# bpf-3rd-order.net
KiCad netlist of a schematic drawn in EAGLE
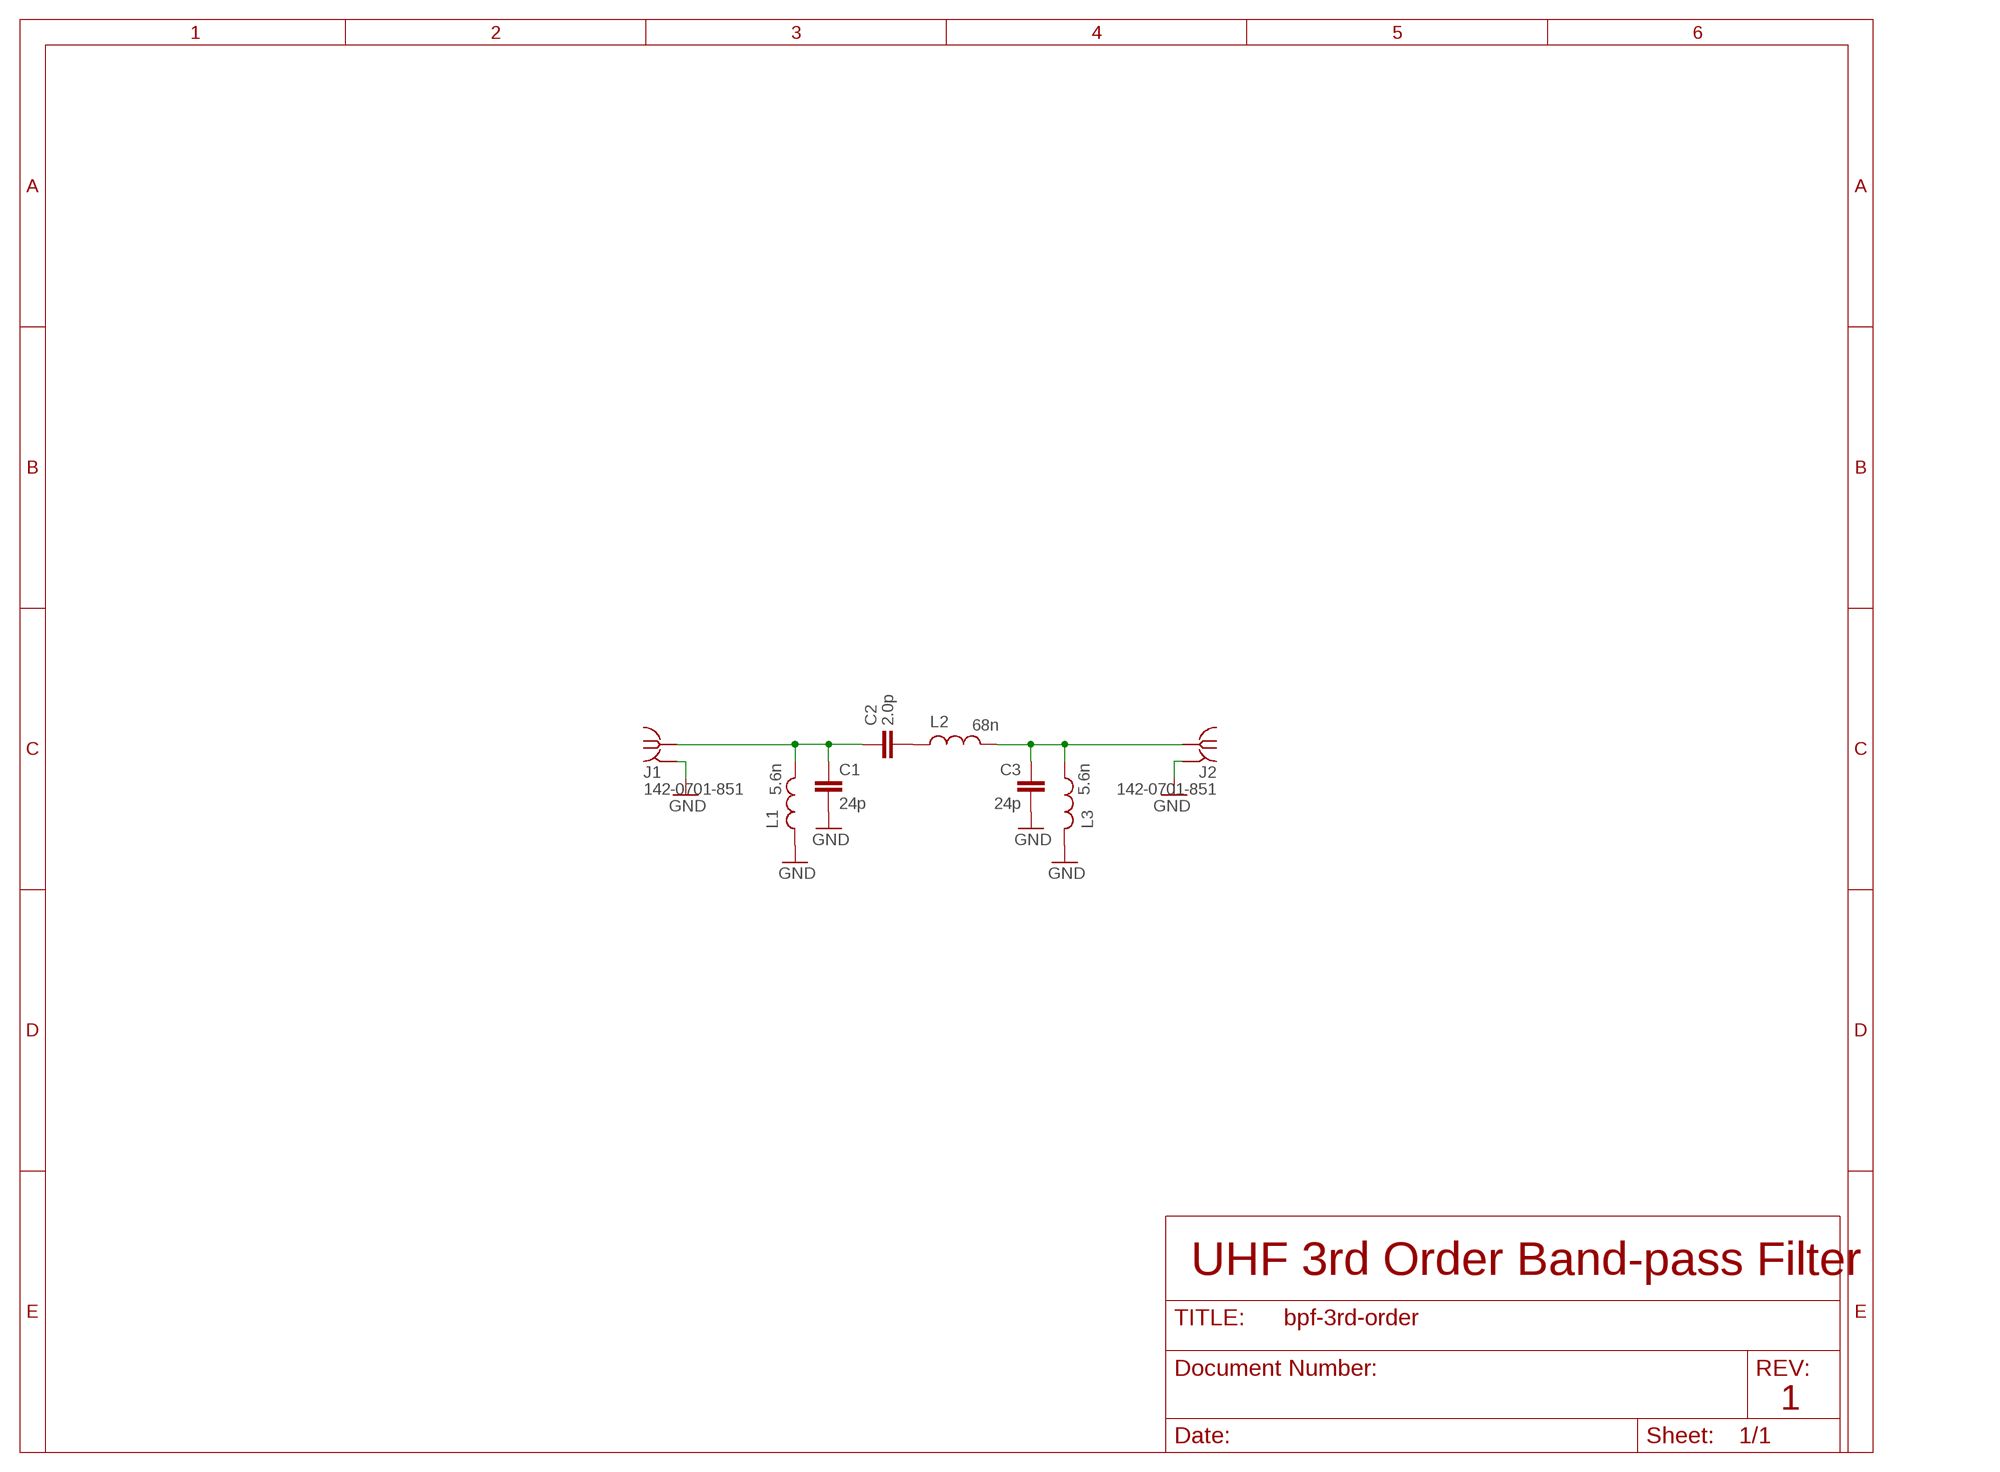
[diagram p0: schematic, sheet 1]

(export (version "E")
  (design (tool "Eeschema 10.0.6"))
  (components
    (comp (ref "C1")
      (value "24p")
      (footprint "eagle-import:.0402-C-NOSILK")
      (libsource (lib "eagle-import") (part "C-EU0402-C-NOSILK"))
    )
    (comp (ref "C2")
      (value "2.0p")
      (footprint "eagle-import:.0402-C-NOSILK")
      (libsource (lib "eagle-import") (part "C-EU0402-C-NOSILK"))
    )
    (comp (ref "C3")
      (value "24p")
      (footprint "eagle-import:.0402-C-NOSILK")
      (libsource (lib "eagle-import") (part "C-EU0402-C-NOSILK"))
    )
    (comp (ref "J1")
      (value "142-0701-851")
      (footprint "eagle-import:142-0701-851")
      (libsource (lib "eagle-import") (part "142-0701-851"))
    )
    (comp (ref "J2")
      (value "142-0701-851")
      (footprint "eagle-import:142-0701-851")
      (libsource (lib "eagle-import") (part "142-0701-851"))
    )
    (comp (ref "L1")
      (value "5.6n")
      (footprint "eagle-import:.0402-C-NOSILK")
      (libsource (lib "eagle-import") (part "L-US0402-C-NOSILK"))
    )
    (comp (ref "L2")
      (value "68n")
      (footprint "eagle-import:.0402-C-NOSILK")
      (libsource (lib "eagle-import") (part "L-US0402-C-NOSILK"))
    )
    (comp (ref "L3")
      (value "5.6n")
      (footprint "eagle-import:.0402-C-NOSILK")
      (libsource (lib "eagle-import") (part "L-US0402-C-NOSILK"))
    )
  )
  (nets
    (net (code "1") (name "GND") (class "Default")
      (node (ref "C1") (pin "2") (pinfunction "2_2") (pintype "passive"))
      (node (ref "C3") (pin "2") (pinfunction "2_2") (pintype "passive"))
      (node (ref "J1") (pin "GND1") (pinfunction "GND_GND1") (pintype "bidirectional"))
      (node (ref "J1") (pin "GND2") (pinfunction "GND_GND2") (pintype "bidirectional"))
      (node (ref "J1") (pin "GND3") (pinfunction "GND_GND3") (pintype "bidirectional"))
      (node (ref "J1") (pin "GND4") (pinfunction "GND_GND4") (pintype "bidirectional"))
      (node (ref "J2") (pin "GND1") (pinfunction "GND_GND1") (pintype "bidirectional"))
      (node (ref "J2") (pin "GND2") (pinfunction "GND_GND2") (pintype "bidirectional"))
      (node (ref "J2") (pin "GND3") (pinfunction "GND_GND3") (pintype "bidirectional"))
      (node (ref "J2") (pin "GND4") (pinfunction "GND_GND4") (pintype "bidirectional"))
      (node (ref "L1") (pin "1") (pinfunction "1_1") (pintype "passive"))
      (node (ref "L3") (pin "1") (pinfunction "1_1") (pintype "passive"))
    )
    (net (code "2") (name "Net-(C2-Pad2)") (class "Default")
      (node (ref "C2") (pin "2") (pinfunction "2_2") (pintype "passive"))
      (node (ref "L2") (pin "1") (pinfunction "1_1") (pintype "passive"))
    )
    (net (code "3") (name "Net-(J1-RF)") (class "Default")
      (node (ref "C1") (pin "1") (pinfunction "1_1") (pintype "passive"))
      (node (ref "C2") (pin "1") (pinfunction "1_1") (pintype "passive"))
      (node (ref "J1") (pin "RF1") (pinfunction "RF_RF1") (pintype "bidirectional"))
      (node (ref "L1") (pin "2") (pinfunction "2_2") (pintype "passive"))
    )
    (net (code "4") (name "Net-(J2-RF)") (class "Default")
      (node (ref "C3") (pin "1") (pinfunction "1_1") (pintype "passive"))
      (node (ref "J2") (pin "RF1") (pinfunction "RF_RF1") (pintype "bidirectional"))
      (node (ref "L2") (pin "2") (pinfunction "2_2") (pintype "passive"))
      (node (ref "L3") (pin "2") (pinfunction "2_2") (pintype "passive"))
    )
  )
)
